# MySens-easyESP32-013.net
KiCad netlist of a schematic drawn in EAGLE
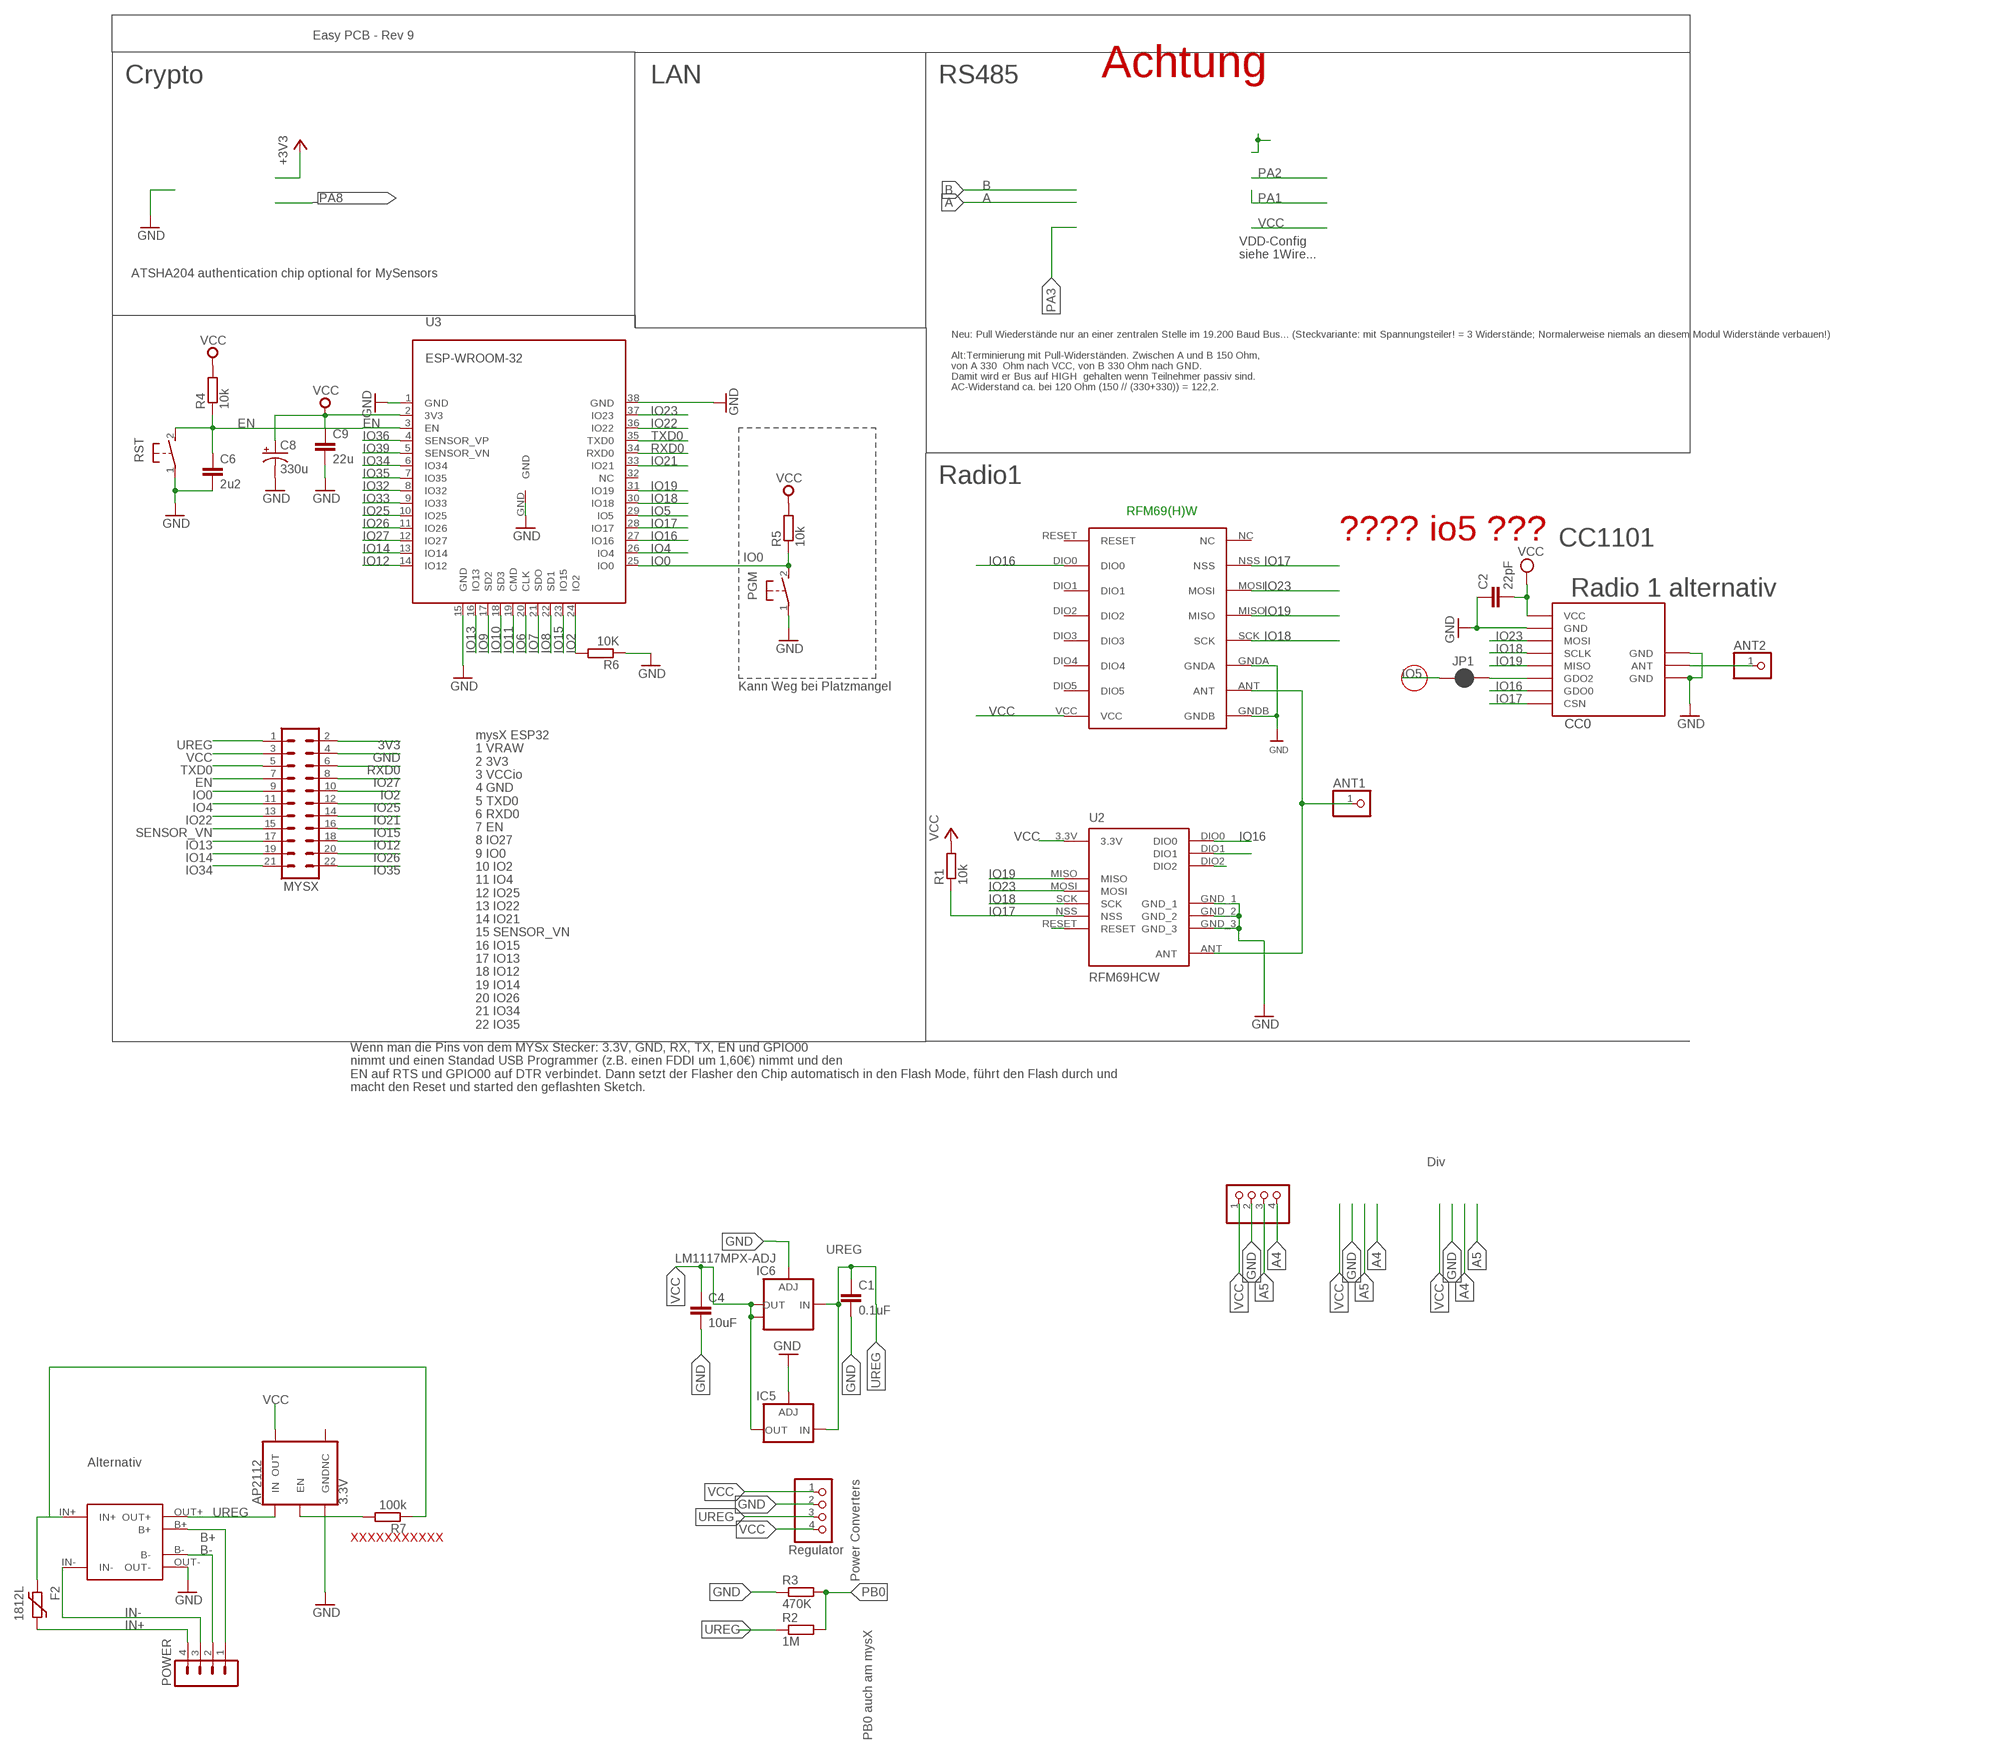
[diagram p0: schematic, sheet 1]

(export (version "E")
  (design (tool "Eeschema 10.0.6"))
  (components
    (comp (ref "ANT1")
      (value "PINHD-1X1")
      (footprint "eagle-import:1X01")
      (libsource (lib "eagle-import") (part "PINHD-1X1"))
    )
    (comp (ref "ANT2")
      (value "PINHD-1X1")
      (footprint "eagle-import:1X01")
      (libsource (lib "eagle-import") (part "PINHD-1X1"))
    )
    (comp (ref "AP2112")
      (value "3.3V")
      (footprint "eagle-import:SOT23-5")
      (libsource (lib "eagle-import") (part "V_REG_AP2112K-3.3V"))
    )
    (comp (ref "C1")
      (value "0.1uF")
      (footprint "eagle-import:C1206")
      (libsource (lib "eagle-import") (part "C-EUC1206"))
    )
    (comp (ref "C2")
      (value "22pF")
      (footprint "eagle-import:C0805")
      (libsource (lib "eagle-import") (part "C-EUC0805"))
    )
    (comp (ref "C4")
      (value "10uF")
      (footprint "eagle-import:C1210")
      (libsource (lib "eagle-import") (part "C-EUC1210"))
    )
    (comp (ref "C6")
      (value "2u2")
      (footprint "eagle-import:C0603")
      (libsource (lib "eagle-import") (part "C-EUC0603"))
    )
    (comp (ref "C8")
      (value "330u")
      (footprint "eagle-import:VISHAY_C")
      (libsource (lib "eagle-import") (part "CAP_POLSMD"))
    )
    (comp (ref "C9")
      (value "22u")
      (footprint "eagle-import:0805")
      (libsource (lib "eagle-import") (part "CAP0805"))
    )
    (comp (ref "CC0")
      (value "CC1101")
      (footprint "eagle-import:CC1101_MODULE1_SMD")
      (libsource (lib "eagle-import") (part "CC1101_MODULE1SMD"))
    )
    (comp (ref "F2")
      (value "1812L")
      (footprint "eagle-import:1812L")
      (libsource (lib "eagle-import") (part "1812L"))
    )
    (comp (ref "I2C-1")
      (value "PINHD-1X04_2.54-S")
      (footprint "eagle-import:1X04-S")
      (libsource (lib "eagle-import") (part "PINHD-1X04_2.54-S"))
    )
    (comp (ref "IC5")
      (value "LD117ADT50TR")
      (footprint "eagle-import:DPACK")
      (libsource (lib "eagle-import") (part "LD117A?DT50TR"))
    )
    (comp (ref "IC6")
      (value "LM1117MPX-ADJ")
      (footprint "eagle-import:SOT223")
      (libsource (lib "eagle-import") (part "LM1117MPX-ADJ"))
    )
    (comp (ref "JP1")
      (value "JUMPER-SMT_2_NC_PASTE_NO-SILK")
      (footprint "eagle-import:SMT-JUMPER_2_NC_PASTE_NO-SILK")
      (libsource (lib "eagle-import") (part "JUMPER-SMT_2_NC_PASTE_NO-SILK"))
    )
    (comp (ref "MYSX")
      (value "MA11-2")
      (footprint "eagle-import:MA11-2")
      (libsource (lib "eagle-import") (part "MA11-2"))
    )
    (comp (ref "PGM")
      (value "DTSM-3")
      (footprint "eagle-import:DTSM-3")
      (libsource (lib "eagle-import") (part "DTSM-3"))
    )
    (comp (ref "POWER")
      (value "MA04-1")
      (footprint "eagle-import:MA04-1")
      (libsource (lib "eagle-import") (part "MA04-1"))
    )
    (comp (ref "R1")
      (value "10k")
      (footprint "eagle-import:M0805")
      (libsource (lib "eagle-import") (part "R-EU_M0805"))
    )
    (comp (ref "R2")
      (value "1M")
      (footprint "eagle-import:R0805")
      (libsource (lib "eagle-import") (part "R-EU_R0805"))
    )
    (comp (ref "R3")
      (value "470K")
      (footprint "eagle-import:R0805")
      (libsource (lib "eagle-import") (part "R-EU_R0805"))
    )
    (comp (ref "R4")
      (value "10k")
      (footprint "eagle-import:R0603")
      (libsource (lib "eagle-import") (part "R-EU_R0603"))
    )
    (comp (ref "R5")
      (value "10k")
      (footprint "eagle-import:R0603")
      (libsource (lib "eagle-import") (part "R-EU_R0603"))
    )
    (comp (ref "R6")
      (value "10K")
      (footprint "eagle-import:R0603")
      (libsource (lib "eagle-import") (part "R-EU_R0603"))
    )
    (comp (ref "R7")
      (value "100k")
      (footprint "eagle-import:M0805")
      (libsource (lib "eagle-import") (part "R-EU_M0805"))
    )
    (comp (ref "RFM69W1")
      (value "RFM69HW")
      (footprint "eagle-import:RFM")
      (libsource (lib "eagle-import") (part "RFM69HW"))
    )
    (comp (ref "RST")
      (value "DTSM-3")
      (footprint "eagle-import:DTSM-3")
      (libsource (lib "eagle-import") (part "DTSM-3"))
    )
    (comp (ref "STEPDWN")
      (value "PINHD-1X04_2.54-S")
      (footprint "eagle-import:1X04-S")
      (libsource (lib "eagle-import") (part "PINHD-1X04_2.54-S"))
    )
    (comp (ref "TP4056")
      (value "TP4056-MODULE")
      (footprint "eagle-import:TP4056-LITHIUM-PROTECTED-MODULE")
      (libsource (lib "eagle-import") (part "TP4056-MODULE"))
    )
    (comp (ref "U2")
      (value "RFM69HCW")
      (footprint "eagle-import:RFM69HCW-XXXS2")
      (libsource (lib "eagle-import") (part "RFM69HCW"))
    )
    (comp (ref "U3")
      (value "ESP-WROOM-32")
      (footprint "eagle-import:ESP-WROOM-32")
      (libsource (lib "eagle-import") (part "ESP-WROOM-32"))
    )
  )
  (nets
    (net (code "2") (name "/3V3") (class "Default")
      (node (ref "MYSX") (pin "2") (pinfunction "2_2") (pintype "passive"))
    )
    (net (code "3") (name "/B+") (class "Default")
      (node (ref "POWER") (pin "1") (pinfunction "1_1") (pintype "passive"))
      (node (ref "TP4056") (pin "B+") (pinfunction "B+_B+") (pintype "power_in"))
    )
    (net (code "4") (name "/B-") (class "Default")
      (node (ref "POWER") (pin "2") (pinfunction "2_2") (pintype "passive"))
      (node (ref "TP4056") (pin "B-") (pinfunction "B-_B-") (pintype "power_in"))
    )
    (net (code "5") (name "/EN") (class "Default")
      (node (ref "C6") (pin "1") (pinfunction "1_1") (pintype "passive"))
      (node (ref "MYSX") (pin "7") (pinfunction "7_7") (pintype "passive"))
      (node (ref "R4") (pin "1") (pinfunction "1_1") (pintype "passive"))
      (node (ref "RST") (pin "2") (pinfunction "2_2") (pintype "passive"))
      (node (ref "U3") (pin "3") (pinfunction "EN_3") (pintype "bidirectional"))
    )
    (net (code "6") (name "/IN+") (class "Default")
      (node (ref "F2") (pin "P$2") (pinfunction "2_P$2") (pintype "passive"))
      (node (ref "POWER") (pin "4") (pinfunction "4_4") (pintype "passive"))
    )
    (net (code "7") (name "/IN-") (class "Default")
      (node (ref "POWER") (pin "3") (pinfunction "3_3") (pintype "passive"))
      (node (ref "TP4056") (pin "IN-") (pinfunction "IN-_IN-") (pintype "power_in"))
    )
    (net (code "8") (name "/IO0") (class "Default")
      (node (ref "MYSX") (pin "9") (pinfunction "9_9") (pintype "passive"))
      (node (ref "PGM") (pin "2") (pinfunction "2_2") (pintype "passive"))
      (node (ref "R5") (pin "1") (pinfunction "1_1") (pintype "passive"))
      (node (ref "U3") (pin "25") (pinfunction "IO0_25") (pintype "bidirectional"))
    )
    (net (code "9") (name "/IO2") (class "Default")
      (node (ref "MYSX") (pin "10") (pinfunction "10_10") (pintype "passive"))
      (node (ref "R6") (pin "2") (pinfunction "2_2") (pintype "passive"))
      (node (ref "U3") (pin "24") (pinfunction "IO2_24") (pintype "bidirectional"))
    )
    (net (code "10") (name "/IO4") (class "Default")
      (node (ref "MYSX") (pin "11") (pinfunction "11_11") (pintype "passive"))
      (node (ref "U3") (pin "26") (pinfunction "IO4_26") (pintype "bidirectional"))
    )
    (net (code "11") (name "/IO5") (class "Default")
      (node (ref "JP1") (pin "1") (pinfunction "1_1") (pintype "passive"))
      (node (ref "U3") (pin "29") (pinfunction "IO5_29") (pintype "bidirectional"))
    )
    (net (code "12") (name "/IO6") (class "Default")
      (node (ref "U3") (pin "20") (pinfunction "CLK_20") (pintype "bidirectional"))
    )
    (net (code "13") (name "/IO7") (class "Default")
      (node (ref "U3") (pin "21") (pinfunction "SDO_21") (pintype "bidirectional"))
    )
    (net (code "14") (name "/IO8") (class "Default")
      (node (ref "U3") (pin "22") (pinfunction "SD1_22") (pintype "bidirectional"))
    )
    (net (code "15") (name "/IO9") (class "Default")
      (node (ref "U3") (pin "17") (pinfunction "SD2_17") (pintype "bidirectional"))
    )
    (net (code "16") (name "/IO10") (class "Default")
      (node (ref "U3") (pin "18") (pinfunction "SD3_18") (pintype "bidirectional"))
    )
    (net (code "17") (name "/IO11") (class "Default")
      (node (ref "U3") (pin "19") (pinfunction "CMD_19") (pintype "bidirectional"))
    )
    (net (code "18") (name "/IO12") (class "Default")
      (node (ref "MYSX") (pin "18") (pinfunction "18_18") (pintype "passive"))
      (node (ref "U3") (pin "14") (pinfunction "IO12_14") (pintype "bidirectional"))
    )
    (net (code "19") (name "/IO13") (class "Default")
      (node (ref "MYSX") (pin "17") (pinfunction "17_17") (pintype "passive"))
      (node (ref "U3") (pin "16") (pinfunction "IO13_16") (pintype "bidirectional"))
    )
    (net (code "20") (name "/IO14") (class "Default")
      (node (ref "MYSX") (pin "19") (pinfunction "19_19") (pintype "passive"))
      (node (ref "U3") (pin "13") (pinfunction "IO14_13") (pintype "bidirectional"))
    )
    (net (code "21") (name "/IO15") (class "Default")
      (node (ref "MYSX") (pin "16") (pinfunction "16_16") (pintype "passive"))
      (node (ref "U3") (pin "23") (pinfunction "IO15_23") (pintype "bidirectional"))
    )
    (net (code "22") (name "/IO16") (class "Default")
      (node (ref "CC0") (pin "GDO0") (pinfunction "GDO0_GDO0") (pintype "bidirectional"))
      (node (ref "RFM69W1") (pin "DIO0") (pinfunction "DIO0_DIO0") (pintype "bidirectional"))
      (node (ref "U2") (pin "DIO0") (pinfunction "DIO0_DIO0") (pintype "bidirectional"))
      (node (ref "U3") (pin "27") (pinfunction "IO16_27") (pintype "bidirectional"))
    )
    (net (code "23") (name "/IO17") (class "Default")
      (node (ref "CC0") (pin "CSN") (pinfunction "CSN_CSN") (pintype "bidirectional"))
      (node (ref "R1") (pin "1") (pinfunction "1_1") (pintype "passive"))
      (node (ref "RFM69W1") (pin "NSS") (pinfunction "NSS_NSS") (pintype "bidirectional"))
      (node (ref "U2") (pin "NSS") (pinfunction "NSS_NSS") (pintype "input"))
      (node (ref "U3") (pin "28") (pinfunction "IO17_28") (pintype "bidirectional"))
    )
    (net (code "24") (name "/IO18") (class "Default")
      (node (ref "CC0") (pin "SCLK") (pinfunction "SCLK_SCLK") (pintype "bidirectional"))
      (node (ref "RFM69W1") (pin "SCK") (pinfunction "SCK_SCK") (pintype "bidirectional"))
      (node (ref "U2") (pin "SCK") (pinfunction "SCK_SCK") (pintype "input"))
      (node (ref "U3") (pin "30") (pinfunction "IO18_30") (pintype "bidirectional"))
    )
    (net (code "25") (name "/IO19") (class "Default")
      (node (ref "CC0") (pin "MISO") (pinfunction "MISO_MISO") (pintype "bidirectional"))
      (node (ref "RFM69W1") (pin "MISO") (pinfunction "MISO_MISO") (pintype "bidirectional"))
      (node (ref "U2") (pin "MISO") (pinfunction "MISO_MISO") (pintype "bidirectional"))
      (node (ref "U3") (pin "31") (pinfunction "IO19_31") (pintype "bidirectional"))
    )
    (net (code "26") (name "/IO21") (class "Default")
      (node (ref "MYSX") (pin "14") (pinfunction "14_14") (pintype "passive"))
      (node (ref "U3") (pin "33") (pinfunction "IO21_33") (pintype "bidirectional"))
    )
    (net (code "27") (name "/IO22") (class "Default")
      (node (ref "MYSX") (pin "13") (pinfunction "13_13") (pintype "passive"))
      (node (ref "U3") (pin "36") (pinfunction "IO22_36") (pintype "bidirectional"))
    )
    (net (code "28") (name "/IO23") (class "Default")
      (node (ref "CC0") (pin "MOSI") (pinfunction "MOSI_MOSI") (pintype "bidirectional"))
      (node (ref "RFM69W1") (pin "MOSI") (pinfunction "MOSI_MOSI") (pintype "bidirectional"))
      (node (ref "U2") (pin "MOSI") (pinfunction "MOSI_MOSI") (pintype "input"))
      (node (ref "U3") (pin "37") (pinfunction "IO23_37") (pintype "bidirectional"))
    )
    (net (code "29") (name "/IO25") (class "Default")
      (node (ref "MYSX") (pin "12") (pinfunction "12_12") (pintype "passive"))
      (node (ref "U3") (pin "10") (pinfunction "IO25_10") (pintype "bidirectional"))
    )
    (net (code "30") (name "/IO26") (class "Default")
      (node (ref "MYSX") (pin "20") (pinfunction "20_20") (pintype "passive"))
      (node (ref "U3") (pin "11") (pinfunction "IO26_11") (pintype "bidirectional"))
    )
    (net (code "31") (name "/IO27") (class "Default")
      (node (ref "MYSX") (pin "8") (pinfunction "8_8") (pintype "passive"))
      (node (ref "U3") (pin "12") (pinfunction "IO27_12") (pintype "bidirectional"))
    )
    (net (code "32") (name "/IO32") (class "Default")
      (node (ref "U3") (pin "8") (pinfunction "IO32_8") (pintype "bidirectional"))
    )
    (net (code "33") (name "/IO33") (class "Default")
      (node (ref "U3") (pin "9") (pinfunction "IO33_9") (pintype "bidirectional"))
    )
    (net (code "34") (name "/IO34") (class "Default")
      (node (ref "MYSX") (pin "21") (pinfunction "21_21") (pintype "passive"))
      (node (ref "U3") (pin "6") (pinfunction "IO34_6") (pintype "bidirectional"))
    )
    (net (code "35") (name "/IO35") (class "Default")
      (node (ref "MYSX") (pin "22") (pinfunction "22_22") (pintype "passive"))
      (node (ref "U3") (pin "7") (pinfunction "IO35_7") (pintype "bidirectional"))
    )
    (net (code "36") (name "/IO36") (class "Default")
      (node (ref "U3") (pin "4") (pinfunction "SENSOR_VP_4") (pintype "bidirectional"))
    )
    (net (code "37") (name "/IO39") (class "Default")
      (node (ref "U3") (pin "5") (pinfunction "SENSOR_VN_5") (pintype "bidirectional"))
    )
    (net (code "41") (name "/RXD0") (class "Default")
      (node (ref "MYSX") (pin "6") (pinfunction "6_6") (pintype "passive"))
      (node (ref "U3") (pin "34") (pinfunction "RXD0_34") (pintype "bidirectional"))
    )
    (net (code "42") (name "/SENSOR_VN") (class "Default")
      (node (ref "MYSX") (pin "15") (pinfunction "15_15") (pintype "passive"))
    )
    (net (code "43") (name "/TXD0") (class "Default")
      (node (ref "MYSX") (pin "5") (pinfunction "5_5") (pintype "passive"))
      (node (ref "U3") (pin "35") (pinfunction "TXD0_35") (pintype "bidirectional"))
    )
    (net (code "45") (name "A4") (class "Default")
      (node (ref "I2C-1") (pin "4") (pinfunction "4_4") (pintype "passive"))
    )
    (net (code "46") (name "A5") (class "Default")
      (node (ref "I2C-1") (pin "3") (pinfunction "3_3") (pintype "passive"))
    )
    (net (code "48") (name "GND") (class "Default")
      (node (ref "AP2112") (pin "2") (pinfunction "GND_2") (pintype "input"))
      (node (ref "C1") (pin "2") (pinfunction "2_2") (pintype "passive"))
      (node (ref "C2") (pin "1") (pinfunction "1_1") (pintype "passive"))
      (node (ref "C4") (pin "2") (pinfunction "2_2") (pintype "passive"))
      (node (ref "C6") (pin "2") (pinfunction "2_2") (pintype "passive"))
      (node (ref "C8") (pin "-") (pinfunction "-_-") (pintype "passive"))
      (node (ref "C9") (pin "2") (pinfunction "2_2") (pintype "passive"))
      (node (ref "CC0") (pin "GND@0") (pinfunction "GND_GND@0") (pintype "power_in"))
      (node (ref "CC0") (pin "GND@1") (pinfunction "GND_GND@1") (pintype "power_in"))
      (node (ref "CC0") (pin "GND@2") (pinfunction "GND_GND@2") (pintype "power_in"))
      (node (ref "I2C-1") (pin "2") (pinfunction "2_2") (pintype "passive"))
      (node (ref "IC5") (pin "1") (pinfunction "ADJ_1") (pintype "input"))
      (node (ref "IC6") (pin "1") (pinfunction "ADJ_1") (pintype "input"))
      (node (ref "MYSX") (pin "4") (pinfunction "4_4") (pintype "passive"))
      (node (ref "PGM") (pin "1") (pinfunction "1_1") (pintype "passive"))
      (node (ref "R3") (pin "1") (pinfunction "1_1") (pintype "passive"))
      (node (ref "R6") (pin "1") (pinfunction "1_1") (pintype "passive"))
      (node (ref "RFM69W1") (pin "GNDA") (pinfunction "GNDA_GNDA") (pintype "bidirectional"))
      (node (ref "RFM69W1") (pin "GNDB") (pinfunction "GNDB_GNDB") (pintype "bidirectional"))
      (node (ref "RST") (pin "1") (pinfunction "1_1") (pintype "passive"))
      (node (ref "STEPDWN") (pin "2") (pinfunction "2_2") (pintype "passive"))
      (node (ref "TP4056") (pin "OUT-") (pinfunction "OUT-_OUT-") (pintype "power_in"))
      (node (ref "U2") (pin "GND_1") (pinfunction "GND_1_GND_1") (pintype "power_in"))
      (node (ref "U2") (pin "GND_2") (pinfunction "GND_2_GND_2") (pintype "power_in"))
      (node (ref "U2") (pin "GND_3") (pinfunction "GND_3_GND_3") (pintype "power_in"))
      (node (ref "U3") (pin "1") (pinfunction "GND_1") (pintype "bidirectional"))
      (node (ref "U3") (pin "15") (pinfunction "GND_15") (pintype "bidirectional"))
      (node (ref "U3") (pin "38") (pinfunction "GND_38") (pintype "bidirectional"))
      (node (ref "U3") (pin "GND") (pinfunction "GND_GND") (pintype "bidirectional"))
    )
    (net (code "49") (name "Net-(ANT1-Pad1)") (class "Default")
      (node (ref "ANT1") (pin "1") (pinfunction "1_1") (pintype "passive"))
      (node (ref "RFM69W1") (pin "ANT") (pinfunction "ANT_ANT") (pintype "bidirectional"))
      (node (ref "U2") (pin "ANT") (pinfunction "ANT_ANT") (pintype "passive"))
    )
    (net (code "50") (name "Net-(ANT2-Pad1)") (class "Default")
      (node (ref "ANT2") (pin "1") (pinfunction "1_1") (pintype "passive"))
      (node (ref "CC0") (pin "ANT") (pinfunction "ANT_ANT") (pintype "output"))
    )
    (net (code "51") (name "Net-(AP2112-EN)") (class "Default")
      (node (ref "AP2112") (pin "3") (pinfunction "EN_3") (pintype "input"))
      (node (ref "R7") (pin "2") (pinfunction "2_2") (pintype "passive"))
    )
    (net (code "52") (name "Net-(CC0-PadGDO2)") (class "Default")
      (node (ref "CC0") (pin "GDO2") (pinfunction "GDO2_GDO2") (pintype "bidirectional"))
      (node (ref "JP1") (pin "2") (pinfunction "2_2") (pintype "passive"))
    )
    (net (code "53") (name "Net-(F2-1)") (class "Default")
      (node (ref "F2") (pin "P$1") (pinfunction "1_P$1") (pintype "passive"))
      (node (ref "R7") (pin "1") (pinfunction "1_1") (pintype "passive"))
      (node (ref "TP4056") (pin "IN+") (pinfunction "IN+_IN+") (pintype "power_in"))
    )
    (net (code "55") (name "PB0") (class "Default")
      (node (ref "R2") (pin "2") (pinfunction "2_2") (pintype "passive"))
      (node (ref "R3") (pin "2") (pinfunction "2_2") (pintype "passive"))
    )
    (net (code "56") (name "UREG") (class "Default")
      (node (ref "AP2112") (pin "1") (pinfunction "IN_1") (pintype "input"))
      (node (ref "C1") (pin "1") (pinfunction "1_1") (pintype "passive"))
      (node (ref "IC5") (pin "3") (pinfunction "IN_3") (pintype "input"))
      (node (ref "IC6") (pin "3") (pinfunction "IN_3") (pintype "input"))
      (node (ref "MYSX") (pin "1") (pinfunction "1_1") (pintype "passive"))
      (node (ref "R2") (pin "1") (pinfunction "1_1") (pintype "passive"))
      (node (ref "STEPDWN") (pin "3") (pinfunction "3_3") (pintype "passive"))
      (node (ref "TP4056") (pin "OUT+") (pinfunction "OUT+_OUT+") (pintype "power_in"))
    )
    (net (code "57") (name "VCC") (class "Default")
      (node (ref "AP2112") (pin "5") (pinfunction "OUT_5") (pintype "passive"))
      (node (ref "C2") (pin "2") (pinfunction "2_2") (pintype "passive"))
      (node (ref "C4") (pin "1") (pinfunction "1_1") (pintype "passive"))
      (node (ref "C8") (pin "+") (pinfunction "+_+") (pintype "passive"))
      (node (ref "C9") (pin "1") (pinfunction "1_1") (pintype "passive"))
      (node (ref "CC0") (pin "VCC") (pinfunction "VCC_VCC") (pintype "power_in"))
      (node (ref "I2C-1") (pin "1") (pinfunction "1_1") (pintype "passive"))
      (node (ref "IC5") (pin "4") (pinfunction "OUT_4") (pintype "passive"))
      (node (ref "IC6") (pin "2") (pinfunction "OUT_2") (pintype "passive"))
      (node (ref "IC6") (pin "TAB") (pinfunction "OUT1_TAB") (pintype "passive"))
      (node (ref "MYSX") (pin "3") (pinfunction "3_3") (pintype "passive"))
      (node (ref "R1") (pin "2") (pinfunction "2_2") (pintype "passive"))
      (node (ref "R4") (pin "2") (pinfunction "2_2") (pintype "passive"))
      (node (ref "R5") (pin "2") (pinfunction "2_2") (pintype "passive"))
      (node (ref "RFM69W1") (pin "VCC") (pinfunction "VCC_VCC") (pintype "bidirectional"))
      (node (ref "STEPDWN") (pin "1") (pinfunction "1_1") (pintype "passive"))
      (node (ref "STEPDWN") (pin "4") (pinfunction "4_4") (pintype "passive"))
      (node (ref "U2") (pin "3.3V") (pinfunction "3.3V_3.3V") (pintype "power_in"))
      (node (ref "U3") (pin "2") (pinfunction "3V3_2") (pintype "bidirectional"))
    )
    (net (code "58") (name "unconnected-(AP2112-NC-Pad4)") (class "Default")
      (node (ref "AP2112") (pin "4") (pinfunction "NC_4") (pintype "no_connect"))
    )
    (net (code "59") (name "unconnected-(RFM69W1-PadDIO1)") (class "Default")
      (node (ref "RFM69W1") (pin "DIO1") (pinfunction "DIO1_DIO1") (pintype "bidirectional"))
    )
    (net (code "60") (name "unconnected-(RFM69W1-PadDIO2)") (class "Default")
      (node (ref "RFM69W1") (pin "DIO2") (pinfunction "DIO2_DIO2") (pintype "bidirectional"))
    )
    (net (code "61") (name "unconnected-(RFM69W1-PadDIO3)") (class "Default")
      (node (ref "RFM69W1") (pin "DIO3") (pinfunction "DIO3_DIO3") (pintype "bidirectional"))
    )
    (net (code "62") (name "unconnected-(RFM69W1-PadDIO4)") (class "Default")
      (node (ref "RFM69W1") (pin "DIO4") (pinfunction "DIO4_DIO4") (pintype "bidirectional"))
    )
    (net (code "63") (name "unconnected-(RFM69W1-PadDIO5)") (class "Default")
      (node (ref "RFM69W1") (pin "DIO5") (pinfunction "DIO5_DIO5") (pintype "bidirectional"))
    )
    (net (code "64") (name "unconnected-(RFM69W1-PadNC)") (class "Default")
      (node (ref "RFM69W1") (pin "NC") (pinfunction "NC_NC") (pintype "bidirectional"))
    )
    (net (code "65") (name "unconnected-(RFM69W1-PadRESET)") (class "Default")
      (node (ref "RFM69W1") (pin "RESET") (pinfunction "RESET_RESET") (pintype "bidirectional"))
    )
    (net (code "66") (name "unconnected-(U2-PadDIO1)") (class "Default")
      (node (ref "U2") (pin "DIO1") (pinfunction "DIO1_DIO1") (pintype "bidirectional"))
    )
    (net (code "67") (name "unconnected-(U2-PadDIO2)") (class "Default")
      (node (ref "U2") (pin "DIO2") (pinfunction "DIO2_DIO2") (pintype "bidirectional"))
    )
    (net (code "68") (name "unconnected-(U2-PadRESET)") (class "Default")
      (node (ref "U2") (pin "RESET") (pinfunction "RESET_RESET") (pintype "input"))
    )
    (net (code "69") (name "unconnected-(U3-NC-Pad32)") (class "Default")
      (node (ref "U3") (pin "32") (pinfunction "NC_32") (pintype "bidirectional"))
    )
  )
)
